# working.net
KiCad netlist of a schematic drawn in EAGLE
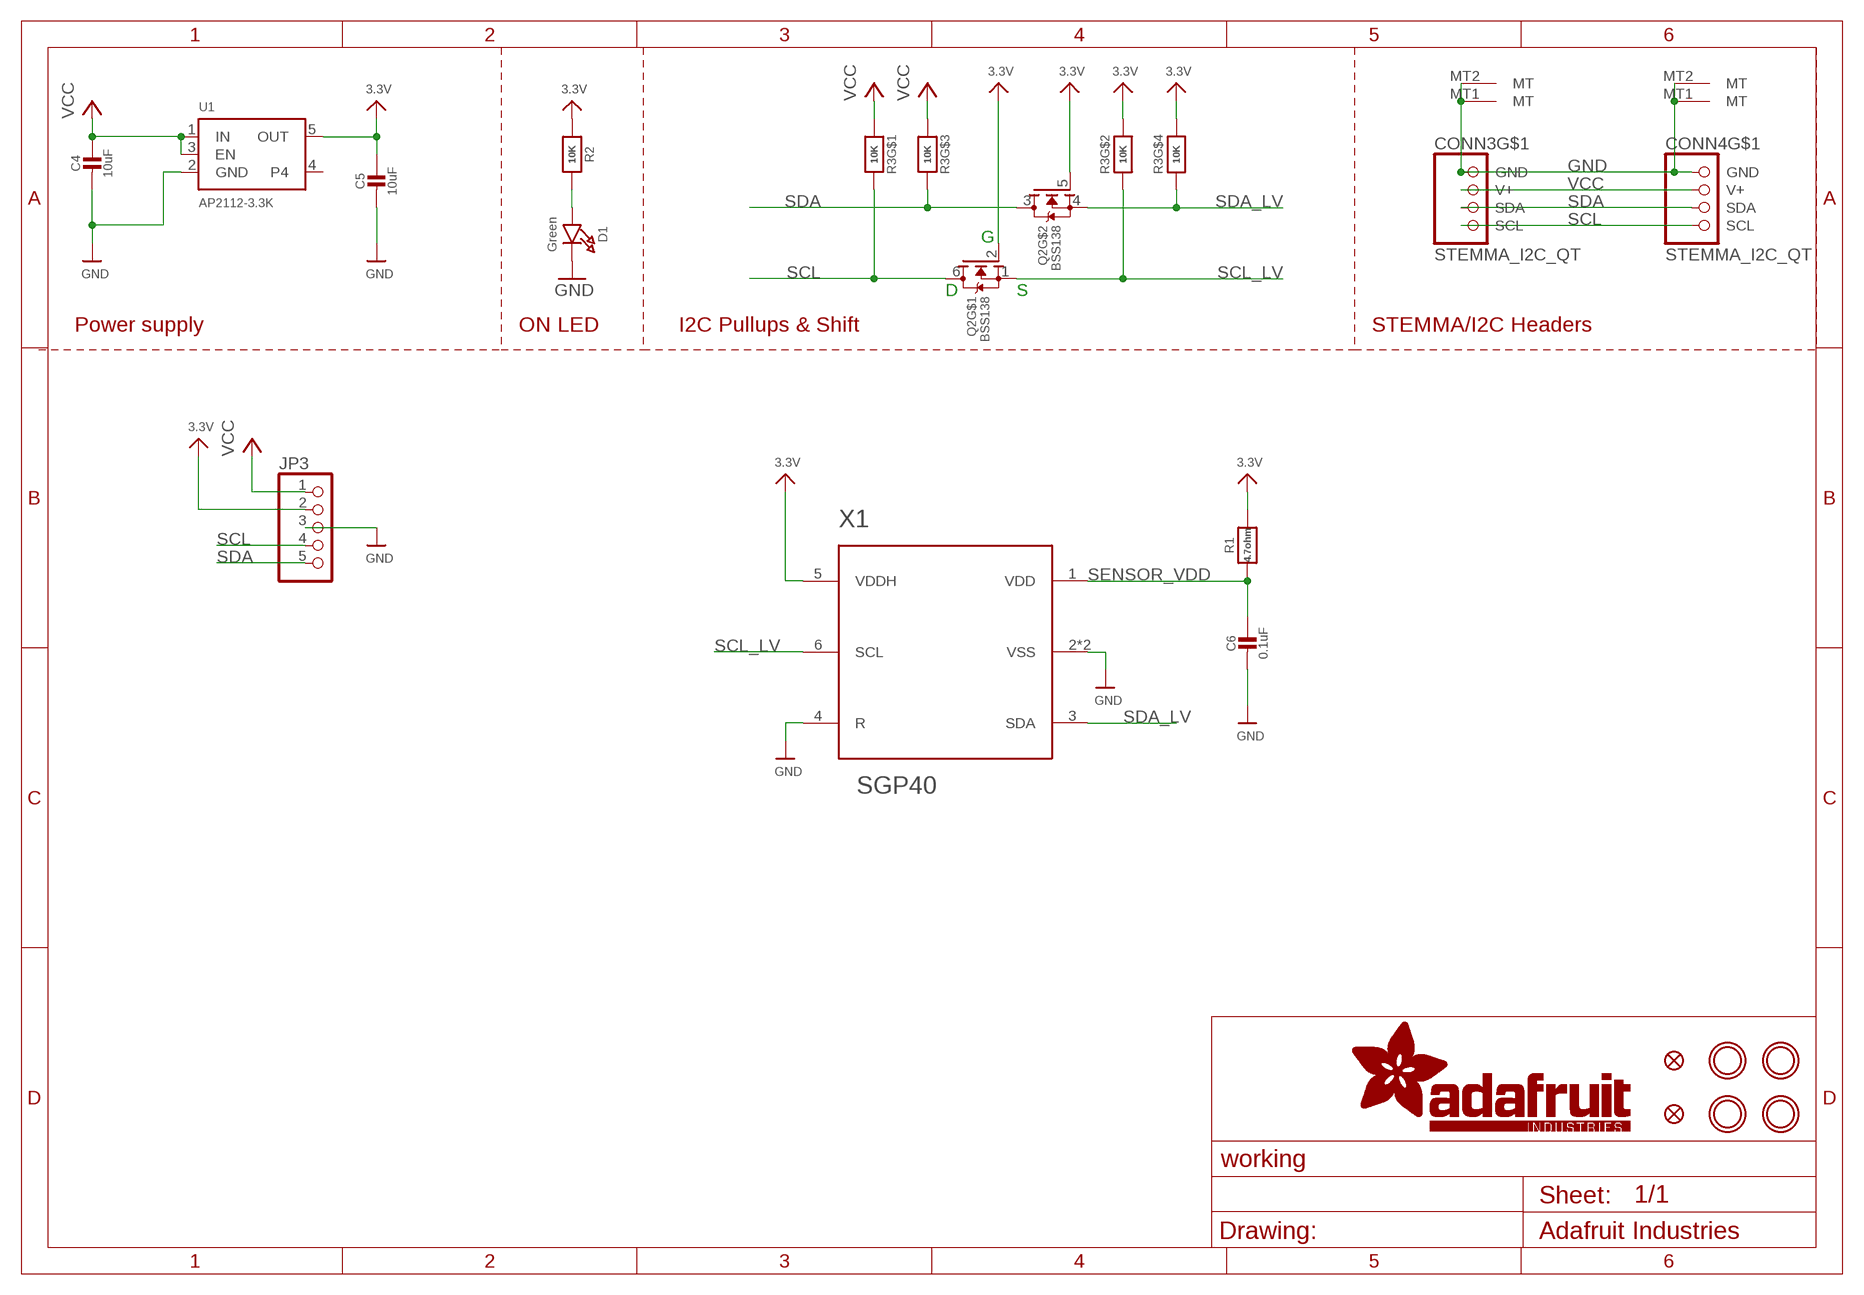
[diagram p0: schematic, sheet 1]

(export (version "E")
  (design (tool "Eeschema 10.0.6"))
  (components
    (comp (ref "C4")
      (value "10uF")
      (footprint "eagle-import:0805-NO")
      (libsource (lib "eagle-import") (part "CAP_CERAMIC0805-NOOUTLINE"))
    )
    (comp (ref "C5")
      (value "10uF")
      (footprint "eagle-import:0805-NO")
      (libsource (lib "eagle-import") (part "CAP_CERAMIC0805-NOOUTLINE"))
    )
    (comp (ref "C6")
      (value "0.1uF")
      (footprint "eagle-import:0603-NO")
      (libsource (lib "eagle-import") (part "CAP_CERAMIC0603_NO"))
    )
    (comp (ref "CONN3")
      (value "STEMMA_I2C_QT")
      (footprint "eagle-import:JST_SH4")
      (libsource (lib "eagle-import") (part "STEMMA_I2C_QT"))
    )
    (comp (ref "CONN4")
      (value "STEMMA_I2C_QT")
      (footprint "eagle-import:JST_SH4")
      (libsource (lib "eagle-import") (part "STEMMA_I2C_QT"))
    )
    (comp (ref "D1")
      (value "Green")
      (footprint "eagle-import:CHIPLED_0603_NOOUTLINE")
      (libsource (lib "eagle-import") (part "LED0603_NOOUTLINE"))
    )
    (comp (ref "FID3")
      (value "FIDUCIAL_1MM")
      (footprint "eagle-import:FIDUCIAL_1MM")
      (libsource (lib "eagle-import") (part "FIDUCIAL_1MM"))
    )
    (comp (ref "FID4")
      (value "FIDUCIAL_1MM")
      (footprint "eagle-import:FIDUCIAL_1MM")
      (libsource (lib "eagle-import") (part "FIDUCIAL_1MM"))
    )
    (comp (ref "JP3")
      (value "HEADER-1X570MIL")
      (footprint "eagle-import:1X05_ROUND_70")
      (libsource (lib "eagle-import") (part "HEADER-1X570MIL"))
    )
    (comp (ref "Q2")
      (value "BSS138")
      (footprint "eagle-import:SOT363")
      (libsource (lib "eagle-import") (part "MOSFET-N_DUAL"))
    )
    (comp (ref "R1")
      (value "4.7ohm")
      (footprint "eagle-import:0603-NO")
      (libsource (lib "eagle-import") (part "RESISTOR_0603_NOOUT"))
    )
    (comp (ref "R2")
      (value "10K")
      (footprint "eagle-import:0603-NO")
      (libsource (lib "eagle-import") (part "RESISTOR_0603_NOOUT"))
    )
    (comp (ref "R3")
      (value "10K")
      (footprint "eagle-import:RESPACK_4X0603")
      (libsource (lib "eagle-import") (part "RESISTOR_4PACK"))
    )
    (comp (ref "U$28")
      (value "MOUNTINGHOLE2.5")
      (footprint "eagle-import:MOUNTINGHOLE_2.5_PLATED")
      (libsource (lib "eagle-import") (part "MOUNTINGHOLE2.5"))
    )
    (comp (ref "U$29")
      (value "MOUNTINGHOLE2.5")
      (footprint "eagle-import:MOUNTINGHOLE_2.5_PLATED")
      (libsource (lib "eagle-import") (part "MOUNTINGHOLE2.5"))
    )
    (comp (ref "U$31")
      (value "MOUNTINGHOLE2.5")
      (footprint "eagle-import:MOUNTINGHOLE_2.5_PLATED")
      (libsource (lib "eagle-import") (part "MOUNTINGHOLE2.5"))
    )
    (comp (ref "U$32")
      (value "MOUNTINGHOLE2.5")
      (footprint "eagle-import:MOUNTINGHOLE_2.5_PLATED")
      (libsource (lib "eagle-import") (part "MOUNTINGHOLE2.5"))
    )
    (comp (ref "U1")
      (value "AP2112-3.3K")
      (footprint "eagle-import:SOT23-5")
      (libsource (lib "eagle-import") (part "VREG_SOT23-5"))
    )
    (comp (ref "X1")
      (value "SGP40")
      (footprint "eagle-import:SGP30")
      (libsource (lib "eagle-import") (part "SGP30"))
    )
  )
  (nets
    (net (code "1") (name "/SCL") (class "Default")
      (node (ref "CONN3") (pin "4") (pinfunction "SCL_4") (pintype "passive"))
      (node (ref "CONN4") (pin "4") (pinfunction "SCL_4") (pintype "passive"))
      (node (ref "JP3") (pin "4") (pinfunction "4_4") (pintype "passive"))
      (node (ref "Q2") (pin "6") (pinfunction "D_6") (pintype "bidirectional"))
      (node (ref "R3") (pin "8") (pinfunction "2_8") (pintype "passive"))
    )
    (net (code "2") (name "/SCL_LV") (class "Default")
      (node (ref "Q2") (pin "1") (pinfunction "S_1") (pintype "bidirectional"))
      (node (ref "R3") (pin "7") (pinfunction "2_7") (pintype "passive"))
      (node (ref "X1") (pin "6") (pinfunction "SCL_6") (pintype "bidirectional"))
    )
    (net (code "3") (name "/SDA") (class "Default")
      (node (ref "CONN3") (pin "3") (pinfunction "SDA_3") (pintype "passive"))
      (node (ref "CONN4") (pin "3") (pinfunction "SDA_3") (pintype "passive"))
      (node (ref "JP3") (pin "5") (pinfunction "5_5") (pintype "passive"))
      (node (ref "Q2") (pin "3") (pinfunction "D_3") (pintype "bidirectional"))
      (node (ref "R3") (pin "6") (pinfunction "2_6") (pintype "passive"))
    )
    (net (code "4") (name "/SDA_LV") (class "Default")
      (node (ref "Q2") (pin "4") (pinfunction "S_4") (pintype "bidirectional"))
      (node (ref "R3") (pin "5") (pinfunction "2_5") (pintype "passive"))
      (node (ref "X1") (pin "3") (pinfunction "SDA_3") (pintype "bidirectional"))
    )
    (net (code "5") (name "/SENSOR_VDD") (class "Default")
      (node (ref "C6") (pin "1") (pinfunction "1_1") (pintype "passive"))
      (node (ref "R1") (pin "1") (pinfunction "1_1") (pintype "passive"))
      (node (ref "X1") (pin "1") (pinfunction "VDD_1") (pintype "bidirectional"))
    )
    (net (code "6") (name "3.3V") (class "Default")
      (node (ref "C5") (pin "1") (pinfunction "1_1") (pintype "passive"))
      (node (ref "JP3") (pin "2") (pinfunction "2_2") (pintype "passive"))
      (node (ref "Q2") (pin "2") (pinfunction "G_2") (pintype "bidirectional"))
      (node (ref "Q2") (pin "5") (pinfunction "G_5") (pintype "bidirectional"))
      (node (ref "R1") (pin "2") (pinfunction "2_2") (pintype "passive"))
      (node (ref "R2") (pin "1") (pinfunction "1_1") (pintype "passive"))
      (node (ref "R3") (pin "2") (pinfunction "1_2") (pintype "passive"))
      (node (ref "R3") (pin "4") (pinfunction "1_4") (pintype "passive"))
      (node (ref "U1") (pin "5") (pinfunction "OUT_5") (pintype "power_in"))
      (node (ref "X1") (pin "5") (pinfunction "VDDH_5") (pintype "bidirectional"))
    )
    (net (code "7") (name "GND") (class "Default")
      (node (ref "C4") (pin "2") (pinfunction "2_2") (pintype "passive"))
      (node (ref "C5") (pin "2") (pinfunction "2_2") (pintype "passive"))
      (node (ref "C6") (pin "2") (pinfunction "2_2") (pintype "passive"))
      (node (ref "CONN3") (pin "1") (pinfunction "GND_1") (pintype "passive"))
      (node (ref "CONN3") (pin "MT1") (pinfunction "MT_MT1") (pintype "bidirectional"))
      (node (ref "CONN3") (pin "MT2") (pinfunction "MT_MT2") (pintype "bidirectional"))
      (node (ref "CONN4") (pin "1") (pinfunction "GND_1") (pintype "passive"))
      (node (ref "CONN4") (pin "MT1") (pinfunction "MT_MT1") (pintype "bidirectional"))
      (node (ref "CONN4") (pin "MT2") (pinfunction "MT_MT2") (pintype "bidirectional"))
      (node (ref "D1") (pin "C") (pinfunction "C_C") (pintype "passive"))
      (node (ref "JP3") (pin "3") (pinfunction "3_3") (pintype "passive"))
      (node (ref "U1") (pin "2") (pinfunction "GND_2") (pintype "power_in"))
      (node (ref "X1") (pin "2") (pinfunction "VSS_2") (pintype "bidirectional"))
      (node (ref "X1") (pin "4") (pinfunction "R_4") (pintype "bidirectional"))
      (node (ref "X1") (pin "P$7") (pinfunction "VSS_P$7") (pintype "bidirectional"))
    )
    (net (code "8") (name "Net-(D1-PadA)") (class "Default")
      (node (ref "D1") (pin "A") (pinfunction "A_A") (pintype "passive"))
      (node (ref "R2") (pin "2") (pinfunction "2_2") (pintype "passive"))
    )
    (net (code "9") (name "VCC") (class "Default")
      (node (ref "C4") (pin "1") (pinfunction "1_1") (pintype "passive"))
      (node (ref "CONN3") (pin "2") (pinfunction "V+_2") (pintype "passive"))
      (node (ref "CONN4") (pin "2") (pinfunction "V+_2") (pintype "passive"))
      (node (ref "JP3") (pin "1") (pinfunction "1_1") (pintype "passive"))
      (node (ref "R3") (pin "1") (pinfunction "1_1") (pintype "passive"))
      (node (ref "R3") (pin "3") (pinfunction "1_3") (pintype "passive"))
      (node (ref "U1") (pin "1") (pinfunction "IN_1") (pintype "power_in"))
      (node (ref "U1") (pin "3") (pinfunction "EN_3") (pintype "input"))
    )
    (net (code "10") (name "unconnected-(U1-P4-Pad4)") (class "Default")
      (node (ref "U1") (pin "4") (pinfunction "P4_4") (pintype "bidirectional"))
    )
  )
)
